# beaglebone.net
KiCad netlist of a schematic drawn in Altium Designer
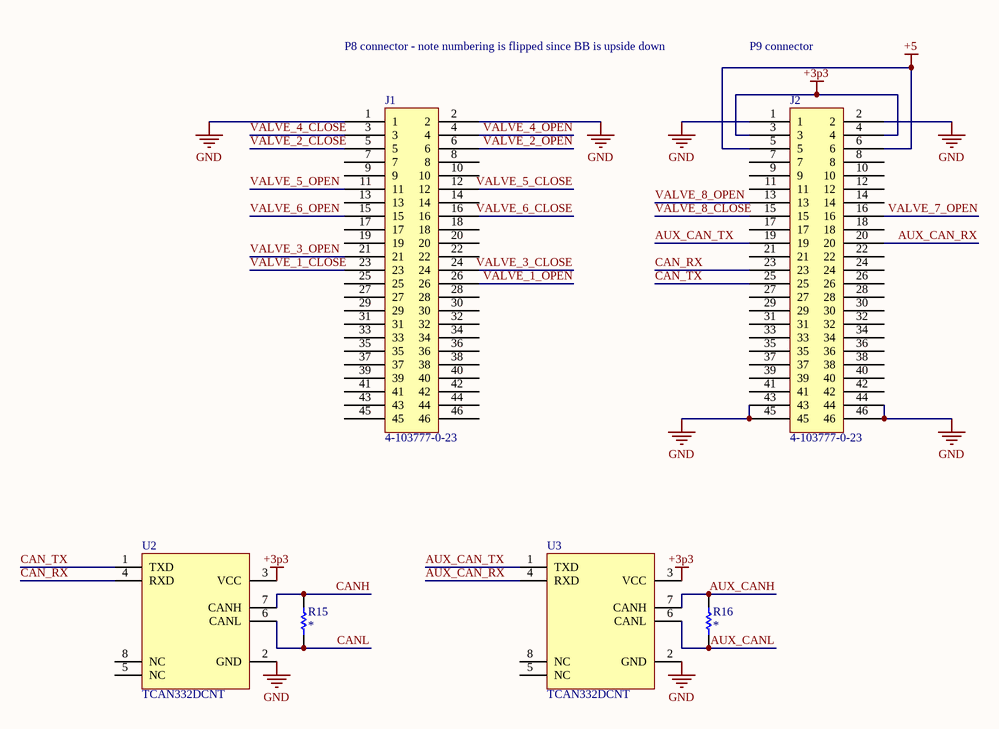
[diagram p0: beaglebone.SchDoc]

(export (version "E")
  (design (tool "Eeschema 10.0.6"))
  (components
    (comp (ref "J1") (value "4-103777-0-23") (libsource (lib "PARSEC") (part "4-103777-0-23")))
    (comp (ref "J2") (value "4-103777-0-23") (libsource (lib "PARSEC") (part "4-103777-0-23")))
    (comp (ref "R15")
      (value "*")
      (footprint "R0603")
      (description "RESISTOR 0603")
      (fields (field (name "ALTIUM_VALUE") "*"))
      (libsource (lib "PARSEC") (part "R0603"))
    )
    (comp (ref "R16")
      (value "*")
      (footprint "R0603")
      (description "RESISTOR 0603")
      (fields (field (name "ALTIUM_VALUE") "*"))
      (libsource (lib "PARSEC") (part "R0603"))
    )
    (comp (ref "U2")
      (value "TCAN332DCNT")
      (footprint "SOT-23-8")
      (description "IC TXRX CAN 3.3V SOT23-8")
      (libsource (lib "PARSEC") (part "TCAN332DCNT"))
    )
    (comp (ref "U3")
      (value "TCAN332DCNT")
      (footprint "SOT-23-8")
      (description "IC TXRX CAN 3.3V SOT23-8")
      (libsource (lib "PARSEC") (part "TCAN332DCNT"))
    )
  )
  (nets
    (net (code "1") (name "+3p3") (class "Default")
      (node (ref "J2") (pin "3") (pinfunction "3_3") (pintype "passive"))
      (node (ref "J2") (pin "4") (pinfunction "4_4") (pintype "passive"))
      (node (ref "U2") (pin "3") (pinfunction "VCC_3") (pintype "passive"))
      (node (ref "U3") (pin "3") (pinfunction "VCC_3") (pintype "passive"))
    )
    (net (code "2") (name "+5") (class "Default")
      (node (ref "J2") (pin "5") (pinfunction "5_5") (pintype "passive"))
      (node (ref "J2") (pin "6") (pinfunction "6_6") (pintype "passive"))
    )
    (net (code "3") (name "/AUX_CANH") (class "Default")
      (node (ref "R16") (pin "1") (pinfunction "1_1") (pintype "passive"))
      (node (ref "U3") (pin "7") (pinfunction "CANH_7") (pintype "passive"))
    )
    (net (code "4") (name "/AUX_CANL") (class "Default")
      (node (ref "R16") (pin "2") (pinfunction "2_2") (pintype "passive"))
      (node (ref "U3") (pin "6") (pinfunction "CANL_6") (pintype "passive"))
    )
    (net (code "5") (name "/AUX_CAN_RX") (class "Default")
      (node (ref "J2") (pin "20") (pinfunction "20_20") (pintype "passive"))
      (node (ref "U3") (pin "4") (pinfunction "RXD_4") (pintype "passive"))
    )
    (net (code "6") (name "/AUX_CAN_TX") (class "Default")
      (node (ref "J2") (pin "19") (pinfunction "19_19") (pintype "passive"))
      (node (ref "U3") (pin "1") (pinfunction "TXD_1") (pintype "passive"))
    )
    (net (code "7") (name "/CANH") (class "Default")
      (node (ref "R15") (pin "1") (pinfunction "1_1") (pintype "passive"))
      (node (ref "U2") (pin "7") (pinfunction "CANH_7") (pintype "passive"))
    )
    (net (code "8") (name "/CANL") (class "Default")
      (node (ref "R15") (pin "2") (pinfunction "2_2") (pintype "passive"))
      (node (ref "U2") (pin "6") (pinfunction "CANL_6") (pintype "passive"))
    )
    (net (code "9") (name "/CAN_RX") (class "Default")
      (node (ref "J2") (pin "23") (pinfunction "23_23") (pintype "passive"))
      (node (ref "U2") (pin "4") (pinfunction "RXD_4") (pintype "passive"))
    )
    (net (code "10") (name "/CAN_TX") (class "Default")
      (node (ref "J2") (pin "25") (pinfunction "25_25") (pintype "passive"))
      (node (ref "U2") (pin "1") (pinfunction "TXD_1") (pintype "passive"))
    )
    (net (code "11") (name "/VALVE_1_CLOSE") (class "Default")
      (node (ref "J1") (pin "23") (pinfunction "23_23") (pintype "passive"))
    )
    (net (code "12") (name "/VALVE_1_OPEN") (class "Default")
      (node (ref "J1") (pin "26") (pinfunction "26_26") (pintype "passive"))
    )
    (net (code "13") (name "/VALVE_2_CLOSE") (class "Default")
      (node (ref "J1") (pin "5") (pinfunction "5_5") (pintype "passive"))
    )
    (net (code "14") (name "/VALVE_2_OPEN") (class "Default")
      (node (ref "J1") (pin "6") (pinfunction "6_6") (pintype "passive"))
    )
    (net (code "15") (name "/VALVE_3_CLOSE") (class "Default")
      (node (ref "J1") (pin "24") (pinfunction "24_24") (pintype "passive"))
    )
    (net (code "16") (name "/VALVE_3_OPEN") (class "Default")
      (node (ref "J1") (pin "21") (pinfunction "21_21") (pintype "passive"))
    )
    (net (code "17") (name "/VALVE_4_CLOSE") (class "Default")
      (node (ref "J1") (pin "3") (pinfunction "3_3") (pintype "passive"))
    )
    (net (code "18") (name "/VALVE_4_OPEN") (class "Default")
      (node (ref "J1") (pin "4") (pinfunction "4_4") (pintype "passive"))
    )
    (net (code "19") (name "/VALVE_5_CLOSE") (class "Default")
      (node (ref "J1") (pin "12") (pinfunction "12_12") (pintype "passive"))
    )
    (net (code "20") (name "/VALVE_5_OPEN") (class "Default")
      (node (ref "J1") (pin "11") (pinfunction "11_11") (pintype "passive"))
    )
    (net (code "21") (name "/VALVE_6_CLOSE") (class "Default")
      (node (ref "J1") (pin "16") (pinfunction "16_16") (pintype "passive"))
    )
    (net (code "22") (name "/VALVE_6_OPEN") (class "Default")
      (node (ref "J1") (pin "15") (pinfunction "15_15") (pintype "passive"))
    )
    (net (code "23") (name "/VALVE_7_OPEN") (class "Default")
      (node (ref "J2") (pin "16") (pinfunction "16_16") (pintype "passive"))
    )
    (net (code "24") (name "/VALVE_8_CLOSE") (class "Default")
      (node (ref "J2") (pin "15") (pinfunction "15_15") (pintype "passive"))
    )
    (net (code "25") (name "/VALVE_8_OPEN") (class "Default")
      (node (ref "J2") (pin "13") (pinfunction "13_13") (pintype "passive"))
    )
    (net (code "26") (name "GND") (class "Default")
      (node (ref "J1") (pin "1") (pinfunction "1_1") (pintype "passive"))
      (node (ref "J1") (pin "2") (pinfunction "2_2") (pintype "passive"))
      (node (ref "J2") (pin "1") (pinfunction "1_1") (pintype "passive"))
      (node (ref "J2") (pin "2") (pinfunction "2_2") (pintype "passive"))
      (node (ref "J2") (pin "43") (pinfunction "43_43") (pintype "passive"))
      (node (ref "J2") (pin "44") (pinfunction "44_44") (pintype "passive"))
      (node (ref "J2") (pin "45") (pinfunction "45_45") (pintype "passive"))
      (node (ref "J2") (pin "46") (pinfunction "46_46") (pintype "passive"))
      (node (ref "U2") (pin "2") (pinfunction "GND_2") (pintype "passive"))
      (node (ref "U3") (pin "2") (pinfunction "GND_2") (pintype "passive"))
    )
    (net (code "27") (name "unconnected-(J1-Pad7)") (class "Default")
      (node (ref "J1") (pin "7") (pinfunction "7_7") (pintype "passive"))
    )
    (net (code "28") (name "unconnected-(J1-Pad8)") (class "Default")
      (node (ref "J1") (pin "8") (pinfunction "8_8") (pintype "passive"))
    )
    (net (code "29") (name "unconnected-(J1-Pad9)") (class "Default")
      (node (ref "J1") (pin "9") (pinfunction "9_9") (pintype "passive"))
    )
    (net (code "30") (name "unconnected-(J1-Pad10)") (class "Default")
      (node (ref "J1") (pin "10") (pinfunction "10_10") (pintype "passive"))
    )
    (net (code "31") (name "unconnected-(J1-Pad13)") (class "Default")
      (node (ref "J1") (pin "13") (pinfunction "13_13") (pintype "passive"))
    )
    (net (code "32") (name "unconnected-(J1-Pad14)") (class "Default")
      (node (ref "J1") (pin "14") (pinfunction "14_14") (pintype "passive"))
    )
    (net (code "33") (name "unconnected-(J1-Pad17)") (class "Default")
      (node (ref "J1") (pin "17") (pinfunction "17_17") (pintype "passive"))
    )
    (net (code "34") (name "unconnected-(J1-Pad18)") (class "Default")
      (node (ref "J1") (pin "18") (pinfunction "18_18") (pintype "passive"))
    )
    (net (code "35") (name "unconnected-(J1-Pad19)") (class "Default")
      (node (ref "J1") (pin "19") (pinfunction "19_19") (pintype "passive"))
    )
    (net (code "36") (name "unconnected-(J1-Pad20)") (class "Default")
      (node (ref "J1") (pin "20") (pinfunction "20_20") (pintype "passive"))
    )
    (net (code "37") (name "unconnected-(J1-Pad22)") (class "Default")
      (node (ref "J1") (pin "22") (pinfunction "22_22") (pintype "passive"))
    )
    (net (code "38") (name "unconnected-(J1-Pad25)") (class "Default")
      (node (ref "J1") (pin "25") (pinfunction "25_25") (pintype "passive"))
    )
    (net (code "39") (name "unconnected-(J1-Pad27)") (class "Default")
      (node (ref "J1") (pin "27") (pinfunction "27_27") (pintype "passive"))
    )
    (net (code "40") (name "unconnected-(J1-Pad28)") (class "Default")
      (node (ref "J1") (pin "28") (pinfunction "28_28") (pintype "passive"))
    )
    (net (code "41") (name "unconnected-(J1-Pad29)") (class "Default")
      (node (ref "J1") (pin "29") (pinfunction "29_29") (pintype "passive"))
    )
    (net (code "42") (name "unconnected-(J1-Pad30)") (class "Default")
      (node (ref "J1") (pin "30") (pinfunction "30_30") (pintype "passive"))
    )
    (net (code "43") (name "unconnected-(J1-Pad31)") (class "Default")
      (node (ref "J1") (pin "31") (pinfunction "31_31") (pintype "passive"))
    )
    (net (code "44") (name "unconnected-(J1-Pad32)") (class "Default")
      (node (ref "J1") (pin "32") (pinfunction "32_32") (pintype "passive"))
    )
    (net (code "45") (name "unconnected-(J1-Pad33)") (class "Default")
      (node (ref "J1") (pin "33") (pinfunction "33_33") (pintype "passive"))
    )
    (net (code "46") (name "unconnected-(J1-Pad34)") (class "Default")
      (node (ref "J1") (pin "34") (pinfunction "34_34") (pintype "passive"))
    )
    (net (code "47") (name "unconnected-(J1-Pad35)") (class "Default")
      (node (ref "J1") (pin "35") (pinfunction "35_35") (pintype "passive"))
    )
    (net (code "48") (name "unconnected-(J1-Pad36)") (class "Default")
      (node (ref "J1") (pin "36") (pinfunction "36_36") (pintype "passive"))
    )
    (net (code "49") (name "unconnected-(J1-Pad37)") (class "Default")
      (node (ref "J1") (pin "37") (pinfunction "37_37") (pintype "passive"))
    )
    (net (code "50") (name "unconnected-(J1-Pad38)") (class "Default")
      (node (ref "J1") (pin "38") (pinfunction "38_38") (pintype "passive"))
    )
    (net (code "51") (name "unconnected-(J1-Pad39)") (class "Default")
      (node (ref "J1") (pin "39") (pinfunction "39_39") (pintype "passive"))
    )
    (net (code "52") (name "unconnected-(J1-Pad40)") (class "Default")
      (node (ref "J1") (pin "40") (pinfunction "40_40") (pintype "passive"))
    )
    (net (code "53") (name "unconnected-(J1-Pad41)") (class "Default")
      (node (ref "J1") (pin "41") (pinfunction "41_41") (pintype "passive"))
    )
    (net (code "54") (name "unconnected-(J1-Pad42)") (class "Default")
      (node (ref "J1") (pin "42") (pinfunction "42_42") (pintype "passive"))
    )
    (net (code "55") (name "unconnected-(J1-Pad43)") (class "Default")
      (node (ref "J1") (pin "43") (pinfunction "43_43") (pintype "passive"))
    )
    (net (code "56") (name "unconnected-(J1-Pad44)") (class "Default")
      (node (ref "J1") (pin "44") (pinfunction "44_44") (pintype "passive"))
    )
    (net (code "57") (name "unconnected-(J1-Pad45)") (class "Default")
      (node (ref "J1") (pin "45") (pinfunction "45_45") (pintype "passive"))
    )
    (net (code "58") (name "unconnected-(J1-Pad46)") (class "Default")
      (node (ref "J1") (pin "46") (pinfunction "46_46") (pintype "passive"))
    )
    (net (code "59") (name "unconnected-(J2-Pad7)") (class "Default")
      (node (ref "J2") (pin "7") (pinfunction "7_7") (pintype "passive"))
    )
    (net (code "60") (name "unconnected-(J2-Pad8)") (class "Default")
      (node (ref "J2") (pin "8") (pinfunction "8_8") (pintype "passive"))
    )
    (net (code "61") (name "unconnected-(J2-Pad9)") (class "Default")
      (node (ref "J2") (pin "9") (pinfunction "9_9") (pintype "passive"))
    )
    (net (code "62") (name "unconnected-(J2-Pad10)") (class "Default")
      (node (ref "J2") (pin "10") (pinfunction "10_10") (pintype "passive"))
    )
    (net (code "63") (name "unconnected-(J2-Pad11)") (class "Default")
      (node (ref "J2") (pin "11") (pinfunction "11_11") (pintype "passive"))
    )
    (net (code "64") (name "unconnected-(J2-Pad12)") (class "Default")
      (node (ref "J2") (pin "12") (pinfunction "12_12") (pintype "passive"))
    )
    (net (code "65") (name "unconnected-(J2-Pad14)") (class "Default")
      (node (ref "J2") (pin "14") (pinfunction "14_14") (pintype "passive"))
    )
    (net (code "66") (name "unconnected-(J2-Pad17)") (class "Default")
      (node (ref "J2") (pin "17") (pinfunction "17_17") (pintype "passive"))
    )
    (net (code "67") (name "unconnected-(J2-Pad18)") (class "Default")
      (node (ref "J2") (pin "18") (pinfunction "18_18") (pintype "passive"))
    )
    (net (code "68") (name "unconnected-(J2-Pad21)") (class "Default")
      (node (ref "J2") (pin "21") (pinfunction "21_21") (pintype "passive"))
    )
    (net (code "69") (name "unconnected-(J2-Pad22)") (class "Default")
      (node (ref "J2") (pin "22") (pinfunction "22_22") (pintype "passive"))
    )
    (net (code "70") (name "unconnected-(J2-Pad24)") (class "Default")
      (node (ref "J2") (pin "24") (pinfunction "24_24") (pintype "passive"))
    )
    (net (code "71") (name "unconnected-(J2-Pad26)") (class "Default")
      (node (ref "J2") (pin "26") (pinfunction "26_26") (pintype "passive"))
    )
    (net (code "72") (name "unconnected-(J2-Pad27)") (class "Default")
      (node (ref "J2") (pin "27") (pinfunction "27_27") (pintype "passive"))
    )
    (net (code "73") (name "unconnected-(J2-Pad28)") (class "Default")
      (node (ref "J2") (pin "28") (pinfunction "28_28") (pintype "passive"))
    )
    (net (code "74") (name "unconnected-(J2-Pad29)") (class "Default")
      (node (ref "J2") (pin "29") (pinfunction "29_29") (pintype "passive"))
    )
    (net (code "75") (name "unconnected-(J2-Pad30)") (class "Default")
      (node (ref "J2") (pin "30") (pinfunction "30_30") (pintype "passive"))
    )
    (net (code "76") (name "unconnected-(J2-Pad31)") (class "Default")
      (node (ref "J2") (pin "31") (pinfunction "31_31") (pintype "passive"))
    )
    (net (code "77") (name "unconnected-(J2-Pad32)") (class "Default")
      (node (ref "J2") (pin "32") (pinfunction "32_32") (pintype "passive"))
    )
    (net (code "78") (name "unconnected-(J2-Pad33)") (class "Default")
      (node (ref "J2") (pin "33") (pinfunction "33_33") (pintype "passive"))
    )
    (net (code "79") (name "unconnected-(J2-Pad34)") (class "Default")
      (node (ref "J2") (pin "34") (pinfunction "34_34") (pintype "passive"))
    )
    (net (code "80") (name "unconnected-(J2-Pad35)") (class "Default")
      (node (ref "J2") (pin "35") (pinfunction "35_35") (pintype "passive"))
    )
    (net (code "81") (name "unconnected-(J2-Pad36)") (class "Default")
      (node (ref "J2") (pin "36") (pinfunction "36_36") (pintype "passive"))
    )
    (net (code "82") (name "unconnected-(J2-Pad37)") (class "Default")
      (node (ref "J2") (pin "37") (pinfunction "37_37") (pintype "passive"))
    )
    (net (code "83") (name "unconnected-(J2-Pad38)") (class "Default")
      (node (ref "J2") (pin "38") (pinfunction "38_38") (pintype "passive"))
    )
    (net (code "84") (name "unconnected-(J2-Pad39)") (class "Default")
      (node (ref "J2") (pin "39") (pinfunction "39_39") (pintype "passive"))
    )
    (net (code "85") (name "unconnected-(J2-Pad40)") (class "Default")
      (node (ref "J2") (pin "40") (pinfunction "40_40") (pintype "passive"))
    )
    (net (code "86") (name "unconnected-(J2-Pad41)") (class "Default")
      (node (ref "J2") (pin "41") (pinfunction "41_41") (pintype "passive"))
    )
    (net (code "87") (name "unconnected-(J2-Pad42)") (class "Default")
      (node (ref "J2") (pin "42") (pinfunction "42_42") (pintype "passive"))
    )
    (net (code "88") (name "unconnected-(U2-NC-Pad5)") (class "Default")
      (node (ref "U2") (pin "5") (pinfunction "NC_5") (pintype "passive"))
    )
    (net (code "89") (name "unconnected-(U2-NC-Pad8)") (class "Default")
      (node (ref "U2") (pin "8") (pinfunction "NC_8") (pintype "passive"))
    )
    (net (code "90") (name "unconnected-(U3-NC-Pad5)") (class "Default")
      (node (ref "U3") (pin "5") (pinfunction "NC_5") (pintype "passive"))
    )
    (net (code "91") (name "unconnected-(U3-NC-Pad8)") (class "Default")
      (node (ref "U3") (pin "8") (pinfunction "NC_8") (pintype "passive"))
    )
  )
)
